# STLINK.net
KiCad netlist of a schematic drawn in Altium Designer
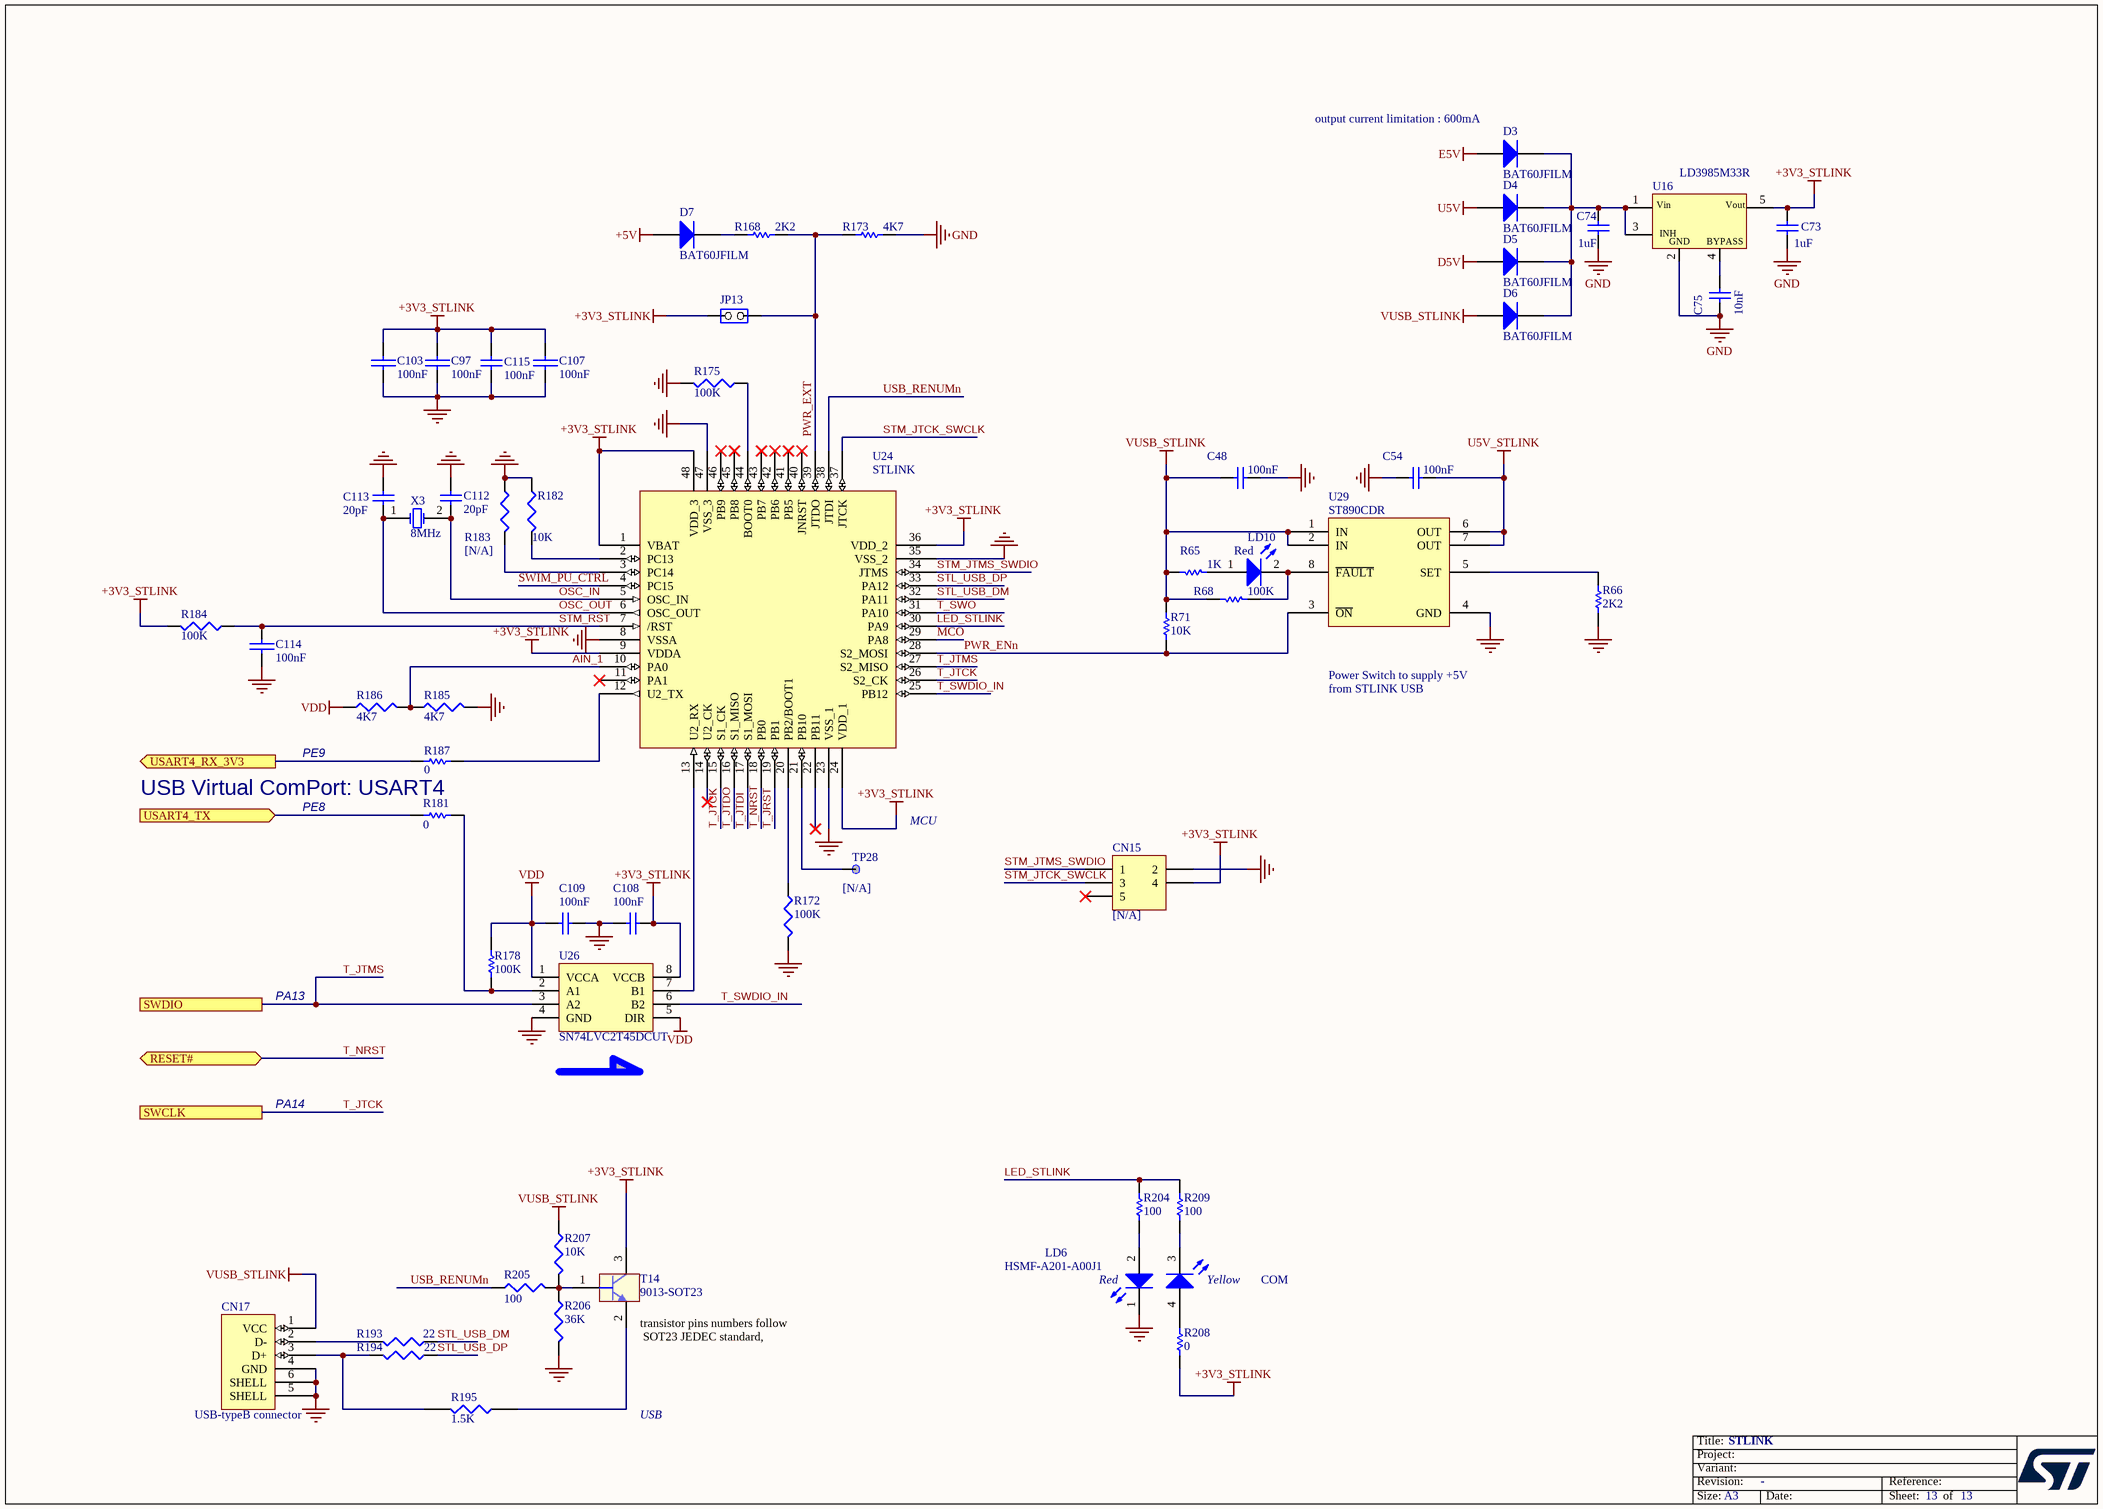
[diagram p0: STLINK.SchDoc]

(export (version "E")
  (design (tool "Eeschema 10.0.6"))
  (components
    (comp (ref "C48")
      (value "100nF")
      (footprint "0402C")
      (description "Capacitor 0402 / 0603 / 0805")
      (libsource (lib "MCD_TOOLS") (part "Capacitor_ST"))
    )
    (comp (ref "C54")
      (value "100nF")
      (footprint "0402C")
      (description "Capacitor 0402 / 0603 / 0805")
      (libsource (lib "MCD_TOOLS") (part "Capacitor_ST"))
    )
    (comp (ref "C73")
      (value "1uF")
      (footprint "0603C")
      (description "Capacitor")
      (fields (field (name "PUBLISHER") "Altium Limited"))
      (libsource (lib "Miscellaneous Devices") (part "CAP"))
    )
    (comp (ref "C74")
      (value "1uF")
      (footprint "0603C")
      (description "Capacitor")
      (fields (field (name "PUBLISHER") "Altium Limited"))
      (libsource (lib "Miscellaneous Devices") (part "CAP"))
    )
    (comp (ref "C75")
      (value "10nF")
      (footprint "0402C")
      (description "Capacitor")
      (fields (field (name "PUBLISHER") "Altium Limited"))
      (libsource (lib "Miscellaneous Devices") (part "Cap"))
    )
    (comp (ref "C97") (value "100nF") (footprint "0402C") (libsource (lib "*") (part "CAP")))
    (comp (ref "C103") (value "100nF") (footprint "0402C") (libsource (lib "*") (part "CAP")))
    (comp (ref "C107") (value "100nF") (footprint "0402C") (libsource (lib "*") (part "CAP")))
    (comp (ref "C108")
      (value "100nF")
      (footprint "0402C")
      (description "Capacitor")
      (fields (field (name "PUBLISHER") "Altium Limited"))
      (libsource (lib "Miscellaneous Devices") (part "CAP"))
    )
    (comp (ref "C109")
      (value "100nF")
      (footprint "0402C")
      (description "Capacitor")
      (fields (field (name "PUBLISHER") "Altium Limited"))
      (libsource (lib "Miscellaneous Devices") (part "CAP"))
    )
    (comp (ref "C112")
      (value "20pF")
      (footprint "0402C")
      (description "Capacitor")
      (fields (field (name "PUBLISHER") "Altium Limited"))
      (libsource (lib "Miscellaneous Devices") (part "CAP"))
    )
    (comp (ref "C113")
      (value "20pF")
      (footprint "0402C")
      (description "Capacitor")
      (fields (field (name "PUBLISHER") "Altium Limited"))
      (libsource (lib "Miscellaneous Devices") (part "CAP"))
    )
    (comp (ref "C114") (value "100nF") (footprint "0402C") (libsource (lib "*") (part "CAP")))
    (comp (ref "C115")
      (value "100nF")
      (footprint "0402C")
      (description "Capacitor")
      (fields (field (name "PUBLISHER") "Altium Limited"))
      (libsource (lib "*") (part "Cap"))
    )
    (comp (ref "CN15")
      (value "[N/A]")
      (footprint "HDR_2X3-1_2R54-6")
      (description "Header, 3-Pin, Dual row")
      (fields (field (name "PUBLISHER") "Altium Limited"))
      (libsource (lib "Miscellaneous Connectors") (part "Header 3X2"))
    )
    (comp (ref "CN17")
      (value "USB-typeB connector")
      (footprint "USB-B")
      (libsource (lib "MB1070") (part "USB-typeB connector"))
    )
    (comp (ref "D3")
      (value "BAT60JFILM")
      (footprint "SOD-323")
      (description "Default Diode")
      (fields (field (name "PUBLISHER") "Altium Limited"))
      (libsource (lib "MB1144_1") (part "Diode"))
    )
    (comp (ref "D4")
      (value "BAT60JFILM")
      (footprint "SOD-323")
      (description "Default Diode")
      (fields (field (name "PUBLISHER") "Altium Limited"))
      (libsource (lib "MB1144_1") (part "Diode"))
    )
    (comp (ref "D5")
      (value "BAT60JFILM")
      (footprint "SOD-323")
      (description "Default Diode")
      (fields (field (name "PUBLISHER") "Altium Limited"))
      (libsource (lib "MB1144_1") (part "Diode"))
    )
    (comp (ref "D6")
      (value "BAT60JFILM")
      (footprint "SOD-323")
      (description "Default Diode")
      (fields (field (name "PUBLISHER") "Altium Limited"))
      (libsource (lib "MB1144_1") (part "Diode"))
    )
    (comp (ref "D7")
      (value "BAT60JFILM")
      (footprint "SOD-323")
      (description "Default Diode")
      (fields (field (name "PUBLISHER") "Altium Limited"))
      (libsource (lib "MB1144_1") (part "Diode"))
    )
    (comp (ref "JP13") (value "~") (footprint "SIP2") (libsource (lib "*") (part "JP2")))
    (comp (ref "LD6")
      (value "HSMF-A201-A00J1")
      (footprint "LED2_3528")
      (fields (field (name "SILKSCREEN") "COM"))
      (libsource (lib "MB819") (part "HSMF-A201-A00J1"))
    )
    (comp (ref "LD10")
      (value "Red")
      (footprint "0603D")
      (description "Typical RED, GREEN, YELLOW, AMBER GaAs LED")
      (fields (field (name "PUBLISHER") "Altium Limited"))
      (libsource (lib "Miscellaneous Devices") (part "LED2"))
    )
    (comp (ref "R65")
      (value "1K")
      (footprint "0402R")
      (description "Resistor")
      (fields (field (name "PUBLISHER") "Altium Limited"))
      (libsource (lib "*") (part "Res1"))
    )
    (comp (ref "R66")
      (value "2K2")
      (footprint "0402R")
      (description "Resistor")
      (fields (field (name "PUBLISHER") "Altium Limited"))
      (libsource (lib "Miscellaneous Devices") (part "res1"))
    )
    (comp (ref "R68")
      (value "100K")
      (footprint "0402R")
      (description "Resistor")
      (fields (field (name "PUBLISHER") "Altium Limited"))
      (libsource (lib "*") (part "Res1"))
    )
    (comp (ref "R71")
      (value "10K")
      (footprint "0402R")
      (description "Resistor")
      (libsource (lib "MCD_TOOLS") (part "Resistor_ST"))
    )
    (comp (ref "R168")
      (value "2K2")
      (footprint "0402R")
      (description "Resistor")
      (fields (field (name "PUBLISHER") "Altium Limited"))
      (libsource (lib "Miscellaneous Devices") (part "res1"))
    )
    (comp (ref "R172")
      (value "100K")
      (footprint "0402R")
      (description "Resistor")
      (libsource (lib "*") (part "RES1"))
    )
    (comp (ref "R173")
      (value "4K7")
      (footprint "0402R")
      (description "Resistor")
      (fields (field (name "PUBLISHER") "Altium Limited"))
      (libsource (lib "Miscellaneous Devices") (part "res1"))
    )
    (comp (ref "R175")
      (value "100K")
      (footprint "0402R")
      (description "Resistor")
      (libsource (lib "*") (part "RES1"))
    )
    (comp (ref "R178")
      (value "100K")
      (footprint "0402R")
      (description "Resistor")
      (fields (field (name "PUBLISHER") "Altium Limited"))
      (libsource (lib "Miscellaneous Devices") (part "Res1"))
    )
    (comp (ref "R181")
      (value "0")
      (footprint "0603R")
      (description "Resistor")
      (fields (field (name "PUBLISHER") "Altium Limited"))
      (libsource (lib "Miscellaneous Devices") (part "Res1"))
    )
    (comp (ref "R182")
      (value "10K")
      (footprint "0402R")
      (description "Resistor")
      (libsource (lib "*") (part "R"))
    )
    (comp (ref "R183") (value "[N/A]") (footprint "0603R") (libsource (lib "*") (part "R")))
    (comp (ref "R184")
      (value "100K")
      (footprint "0402R")
      (description "Resistor")
      (libsource (lib "*") (part "RES1"))
    )
    (comp (ref "R185") (value "4K7") (footprint "0402R") (libsource (lib "*") (part "RES1")))
    (comp (ref "R186") (value "4K7") (footprint "0402R") (libsource (lib "*") (part "RES1")))
    (comp (ref "R187")
      (value "0")
      (footprint "0603R")
      (description "Resistor")
      (fields (field (name "PUBLISHER") "Altium Limited"))
      (libsource (lib "Miscellaneous Devices") (part "Res1"))
    )
    (comp (ref "R193")
      (value "22")
      (footprint "0402R")
      (description "Resistor")
      (libsource (lib "*") (part "RES1"))
    )
    (comp (ref "R194")
      (value "22")
      (footprint "0402R")
      (description "Resistor")
      (libsource (lib "*") (part "RES1"))
    )
    (comp (ref "R195") (value "1.5K") (footprint "0402R") (libsource (lib "") (part "RES1_1")))
    (comp (ref "R204")
      (value "100")
      (footprint "0402R")
      (description "Resistor")
      (fields (field (name "PUBLISHER") "Altium Limited"))
      (libsource (lib "Miscellaneous Devices") (part "Res1"))
    )
    (comp (ref "R205")
      (value "100")
      (footprint "0402R")
      (description "Resistor")
      (libsource (lib "*") (part "R"))
    )
    (comp (ref "R206")
      (value "36K")
      (footprint "0402R")
      (description "Resistor")
      (libsource (lib "*") (part "R"))
    )
    (comp (ref "R207")
      (value "10K")
      (footprint "0402R")
      (description "Resistor")
      (libsource (lib "*") (part "R"))
    )
    (comp (ref "R208")
      (value "0")
      (footprint "0603R")
      (description "Resistor")
      (fields (field (name "PUBLISHER") "Altium Limited"))
      (libsource (lib "Miscellaneous Devices") (part "Res1"))
    )
    (comp (ref "R209")
      (value "100")
      (footprint "0402R")
      (description "Resistor")
      (fields (field (name "PUBLISHER") "Altium Limited"))
      (libsource (lib "Miscellaneous Devices") (part "Res1"))
    )
    (comp (ref "T14")
      (value "9013-SOT23")
      (footprint "SOT-23")
      (description "NPN Bipolar Transistor")
      (libsource (lib "MCD_TOOLS") (part "9013-SOT23"))
    )
    (comp (ref "TP28") (value "[N/A]") (footprint "TP") (libsource (lib "*") (part "TP")))
    (comp (ref "U16")
      (value "LD3985M33R")
      (footprint "SOT23-5")
      (description "Ultra low drop-low noise BiCMOS voltage, regulators low ESR capacitors compatible")
      (libsource (lib "MCD_TOOLS") (part "LD3985M33R"))
    )
    (comp (ref "U24")
      (value "STLINK")
      (footprint "LQFP48_0R5_9X9")
      (libsource (lib "*") (part "STM32F10x(48pin)"))
    )
    (comp (ref "U26")
      (value "SN74LVC2T45DCUT")
      (footprint "USOP8_0R5_2X3R1")
      (libsource (lib "MB818") (part "SN74LVC2T45DCUT"))
    )
    (comp (ref "U29")
      (value "ST890CDR")
      (footprint "SOIC8_1R27_4R9X6")
      (libsource (lib "MB1167") (part "ST890CDR"))
    )
    (comp (ref "X3")
      (value "8MHz")
      (footprint "XTAL_2SM_12R7X4R7")
      (description "Crystal Oscillator")
      (fields (field (name "PUBLISHER") "Altium Limited"))
      (libsource (lib "*") (part "XTAL"))
    )
  )
  (nets
    (net (code "1") (name "+3V3_STLINK") (class "Default")
      (node (ref "C103") (pin "2") (pinfunction "2_2") (pintype "passive"))
      (node (ref "C107") (pin "2") (pinfunction "2_2") (pintype "passive"))
      (node (ref "C108") (pin "1") (pinfunction "1_1") (pintype "passive"))
      (node (ref "C115") (pin "1") (pinfunction "1_1") (pintype "passive"))
      (node (ref "C73") (pin "1") (pinfunction "1_1") (pintype "passive"))
      (node (ref "C97") (pin "2") (pinfunction "2_2") (pintype "passive"))
      (node (ref "CN15") (pin "4") (pinfunction "4_4") (pintype "passive"))
      (node (ref "JP13") (pin "1") (pinfunction "COMMON_1") (pintype "passive"))
      (node (ref "R184") (pin "2") (pinfunction "2_2") (pintype "passive"))
      (node (ref "R208") (pin "2") (pinfunction "2_2") (pintype "passive"))
      (node (ref "T14") (pin "3") (pinfunction "C_3") (pintype "passive"))
      (node (ref "U16") (pin "5") (pinfunction "Vout_5") (pintype "passive"))
      (node (ref "U24") (pin "1") (pinfunction "VBAT_1") (pintype "power_in"))
      (node (ref "U24") (pin "24") (pinfunction "VDD_1_24") (pintype "power_in"))
      (node (ref "U24") (pin "36") (pinfunction "VDD_2_36") (pintype "power_in"))
      (node (ref "U24") (pin "48") (pinfunction "VDD_3_48") (pintype "power_in"))
      (node (ref "U24") (pin "9") (pinfunction "VDDA_9") (pintype "power_in"))
      (node (ref "U26") (pin "8") (pinfunction "VCCB_8") (pintype "passive"))
    )
    (net (code "2") (name "+5V") (class "Default")
      (node (ref "D7") (pin "1") (pinfunction "A_1") (pintype "passive"))
    )
    (net (code "3") (name "/AIN_1") (class "Default")
      (node (ref "R185") (pin "1") (pinfunction "1_1") (pintype "passive"))
      (node (ref "R186") (pin "2") (pinfunction "2_2") (pintype "passive"))
      (node (ref "U24") (pin "10") (pinfunction "PA0_10") (pintype "bidirectional"))
    )
    (net (code "4") (name "/LED_STLINK") (class "Default")
      (node (ref "R204") (pin "1") (pinfunction "1_1") (pintype "passive"))
      (node (ref "R209") (pin "1") (pinfunction "1_1") (pintype "passive"))
      (node (ref "U24") (pin "30") (pinfunction "PA9_30") (pintype "bidirectional"))
    )
    (net (code "5") (name "/MCO") (class "Default")
      (node (ref "U24") (pin "29") (pinfunction "PA8_29") (pintype "bidirectional"))
    )
    (net (code "6") (name "/OSC_IN") (class "Default")
      (node (ref "C112") (pin "2") (pinfunction "2_2") (pintype "passive"))
      (node (ref "U24") (pin "5") (pinfunction "OSC_IN_5") (pintype "input"))
      (node (ref "X3") (pin "2") (pinfunction "OSC2_2") (pintype "passive"))
    )
    (net (code "7") (name "/OSC_OUT") (class "Default")
      (node (ref "C113") (pin "2") (pinfunction "2_2") (pintype "passive"))
      (node (ref "U24") (pin "6") (pinfunction "OSC_OUT_6") (pintype "output"))
      (node (ref "X3") (pin "1") (pinfunction "OSC1_1") (pintype "passive"))
    )
    (net (code "8") (name "/PWR_ENn") (class "Default")
      (node (ref "R71") (pin "1") (pinfunction "1_1") (pintype "passive"))
      (node (ref "U24") (pin "28") (pinfunction "S2_MOSI_28") (pintype "bidirectional"))
      (node (ref "U29") (pin "3") (pinfunction "~{ON}_3") (pintype "passive"))
    )
    (net (code "9") (name "/PWR_EXT") (class "Default")
      (node (ref "JP13") (pin "2") (pinfunction "NO_2") (pintype "passive"))
      (node (ref "R168") (pin "1") (pinfunction "1_1") (pintype "passive"))
      (node (ref "R173") (pin "2") (pinfunction "2_2") (pintype "passive"))
      (node (ref "U24") (pin "39") (pinfunction "JTDO_39") (pintype "bidirectional"))
    )
    (net (code "10") (name "/STL_USB_DM") (class "Default")
      (node (ref "R193") (pin "1") (pinfunction "1_1") (pintype "passive"))
      (node (ref "U24") (pin "32") (pinfunction "PA11_32") (pintype "bidirectional"))
    )
    (net (code "11") (name "/STL_USB_DP") (class "Default")
      (node (ref "R194") (pin "1") (pinfunction "1_1") (pintype "passive"))
      (node (ref "U24") (pin "33") (pinfunction "PA12_33") (pintype "bidirectional"))
    )
    (net (code "12") (name "/STM_JTCK_SWCLK") (class "Default")
      (node (ref "CN15") (pin "3") (pinfunction "3_3") (pintype "passive"))
      (node (ref "U24") (pin "37") (pinfunction "JTCK_37") (pintype "bidirectional"))
    )
    (net (code "13") (name "/STM_JTMS_SWDIO") (class "Default")
      (node (ref "CN15") (pin "1") (pinfunction "1_1") (pintype "passive"))
      (node (ref "U24") (pin "34") (pinfunction "JTMS_34") (pintype "bidirectional"))
    )
    (net (code "14") (name "/STM_RST") (class "Default")
      (node (ref "C114") (pin "2") (pinfunction "2_2") (pintype "passive"))
      (node (ref "R184") (pin "1") (pinfunction "1_1") (pintype "passive"))
      (node (ref "U24") (pin "7") (pinfunction "/RST_7") (pintype "input"))
    )
    (net (code "15") (name "/SWIM_PU_CTRL") (class "Default")
      (node (ref "U24") (pin "4") (pinfunction "PC15_4") (pintype "bidirectional"))
    )
    (net (code "16") (name "/T_JRST") (class "Default")
      (node (ref "U24") (pin "19") (pinfunction "PB1_19") (pintype "bidirectional"))
    )
    (net (code "17") (name "/T_JTCK") (class "Default")
      (node (ref "U24") (pin "15") (pinfunction "S1_CK_15") (pintype "bidirectional"))
      (node (ref "U24") (pin "26") (pinfunction "S2_CK_26") (pintype "bidirectional"))
    )
    (net (code "18") (name "/T_JTDI") (class "Default")
      (node (ref "U24") (pin "17") (pinfunction "S1_MOSI_17") (pintype "bidirectional"))
    )
    (net (code "19") (name "/T_JTDO") (class "Default")
      (node (ref "U24") (pin "16") (pinfunction "S1_MISO_16") (pintype "bidirectional"))
    )
    (net (code "20") (name "/T_JTMS") (class "Default")
      (node (ref "U24") (pin "27") (pinfunction "S2_MISO_27") (pintype "bidirectional"))
      (node (ref "U26") (pin "3") (pinfunction "A2_3") (pintype "passive"))
    )
    (net (code "21") (name "/T_NRST") (class "Default")
      (node (ref "U24") (pin "18") (pinfunction "PB0_18") (pintype "bidirectional"))
    )
    (net (code "22") (name "/T_SWDIO_IN") (class "Default")
      (node (ref "U24") (pin "25") (pinfunction "PB12_25") (pintype "bidirectional"))
      (node (ref "U26") (pin "6") (pinfunction "B2_6") (pintype "passive"))
    )
    (net (code "23") (name "/T_SWO") (class "Default")
      (node (ref "U24") (pin "31") (pinfunction "PA10_31") (pintype "bidirectional"))
    )
    (net (code "24") (name "/USART4_RX_3V3") (class "Default")
      (node (ref "R187") (pin "2") (pinfunction "2_2") (pintype "passive"))
    )
    (net (code "25") (name "/USART4_TX") (class "Default")
      (node (ref "R181") (pin "1") (pinfunction "1_1") (pintype "passive"))
    )
    (net (code "26") (name "/USB_RENUMn") (class "Default")
      (node (ref "R205") (pin "1") (pinfunction "1_1") (pintype "passive"))
      (node (ref "U24") (pin "38") (pinfunction "JTDI_38") (pintype "bidirectional"))
    )
    (net (code "27") (name "D5V") (class "Default")
      (node (ref "D5") (pin "1") (pinfunction "A_1") (pintype "passive"))
    )
    (net (code "28") (name "E5V") (class "Default")
      (node (ref "D3") (pin "1") (pinfunction "A_1") (pintype "passive"))
    )
    (net (code "29") (name "GND") (class "Default")
      (node (ref "C103") (pin "1") (pinfunction "1_1") (pintype "passive"))
      (node (ref "C107") (pin "1") (pinfunction "1_1") (pintype "passive"))
      (node (ref "C108") (pin "2") (pinfunction "2_2") (pintype "passive"))
      (node (ref "C109") (pin "2") (pinfunction "2_2") (pintype "passive"))
      (node (ref "C112") (pin "1") (pinfunction "1_1") (pintype "passive"))
      (node (ref "C113") (pin "1") (pinfunction "1_1") (pintype "passive"))
      (node (ref "C114") (pin "1") (pinfunction "1_1") (pintype "passive"))
      (node (ref "C115") (pin "2") (pinfunction "2_2") (pintype "passive"))
      (node (ref "C48") (pin "2") (pinfunction "2_2") (pintype "passive"))
      (node (ref "C54") (pin "1") (pinfunction "1_1") (pintype "passive"))
      (node (ref "C73") (pin "2") (pinfunction "2_2") (pintype "passive"))
      (node (ref "C74") (pin "2") (pinfunction "2_2") (pintype "passive"))
      (node (ref "C75") (pin "2") (pinfunction "2_2") (pintype "passive"))
      (node (ref "C97") (pin "1") (pinfunction "1_1") (pintype "passive"))
      (node (ref "CN15") (pin "2") (pinfunction "2_2") (pintype "passive"))
      (node (ref "CN17") (pin "4") (pinfunction "GND_4") (pintype "passive"))
      (node (ref "CN17") (pin "5") (pinfunction "SHELL_5") (pintype "power_in"))
      (node (ref "CN17") (pin "6") (pinfunction "SHELL_6") (pintype "power_in"))
      (node (ref "LD6") (pin "1") (pinfunction "RED_cathode_1") (pintype "passive"))
      (node (ref "R172") (pin "2") (pinfunction "2_2") (pintype "passive"))
      (node (ref "R173") (pin "1") (pinfunction "1_1") (pintype "passive"))
      (node (ref "R175") (pin "2") (pinfunction "2_2") (pintype "passive"))
      (node (ref "R182") (pin "1") (pinfunction "1_1") (pintype "passive"))
      (node (ref "R183") (pin "1") (pinfunction "1_1") (pintype "passive"))
      (node (ref "R185") (pin "2") (pinfunction "2_2") (pintype "passive"))
      (node (ref "R206") (pin "2") (pinfunction "2_2") (pintype "passive"))
      (node (ref "R66") (pin "2") (pinfunction "2_2") (pintype "passive"))
      (node (ref "U16") (pin "2") (pinfunction "GND_2") (pintype "passive"))
      (node (ref "U24") (pin "23") (pinfunction "VSS_1_23") (pintype "passive"))
      (node (ref "U24") (pin "35") (pinfunction "VSS_2_35") (pintype "passive"))
      (node (ref "U24") (pin "47") (pinfunction "VSS_3_47") (pintype "passive"))
      (node (ref "U24") (pin "8") (pinfunction "VSSA_8") (pintype "passive"))
      (node (ref "U26") (pin "4") (pinfunction "GND_4") (pintype "passive"))
      (node (ref "U29") (pin "4") (pinfunction "GND_4") (pintype "passive"))
    )
    (net (code "30") (name "Net-(CN17-D+)") (class "Default")
      (node (ref "CN17") (pin "3") (pinfunction "D+_3") (pintype "bidirectional"))
      (node (ref "R194") (pin "2") (pinfunction "2_2") (pintype "passive"))
      (node (ref "R195") (pin "2") (pinfunction "2_2") (pintype "passive"))
    )
    (net (code "31") (name "Net-(CN17-D-)") (class "Default")
      (node (ref "CN17") (pin "2") (pinfunction "D-_2") (pintype "bidirectional"))
      (node (ref "R193") (pin "2") (pinfunction "2_2") (pintype "passive"))
    )
    (net (code "32") (name "Net-(D3-K)") (class "Default")
      (node (ref "C74") (pin "1") (pinfunction "1_1") (pintype "passive"))
      (node (ref "D3") (pin "2") (pinfunction "K_2") (pintype "passive"))
      (node (ref "D4") (pin "2") (pinfunction "K_2") (pintype "passive"))
      (node (ref "D5") (pin "2") (pinfunction "K_2") (pintype "passive"))
      (node (ref "D6") (pin "2") (pinfunction "K_2") (pintype "passive"))
      (node (ref "U16") (pin "1") (pinfunction "Vin_1") (pintype "passive"))
      (node (ref "U16") (pin "3") (pinfunction "CE_3") (pintype "passive"))
    )
    (net (code "33") (name "Net-(D7-K)") (class "Default")
      (node (ref "D7") (pin "2") (pinfunction "K_2") (pintype "passive"))
      (node (ref "R168") (pin "2") (pinfunction "2_2") (pintype "passive"))
    )
    (net (code "34") (name "Net-(LD6-Red_anode)") (class "Default")
      (node (ref "LD6") (pin "2") (pinfunction "Red_anode_2") (pintype "passive"))
      (node (ref "R204") (pin "2") (pinfunction "2_2") (pintype "passive"))
    )
    (net (code "35") (name "Net-(LD6-YellowGreen_anode)") (class "Default")
      (node (ref "LD6") (pin "4") (pinfunction "YellowGreen_anode_4") (pintype "passive"))
      (node (ref "R208") (pin "1") (pinfunction "1_1") (pintype "passive"))
    )
    (net (code "36") (name "Net-(LD6-YellowGreen_cathode)") (class "Default")
      (node (ref "LD6") (pin "3") (pinfunction "YellowGreen_cathode_3") (pintype "passive"))
      (node (ref "R209") (pin "2") (pinfunction "2_2") (pintype "passive"))
    )
    (net (code "37") (name "Net-(LD10-A)") (class "Default")
      (node (ref "LD10") (pin "1") (pinfunction "A_1") (pintype "passive"))
      (node (ref "R65") (pin "2") (pinfunction "2_2") (pintype "passive"))
    )
    (net (code "38") (name "Net-(LD10-K)") (class "Default")
      (node (ref "LD10") (pin "2") (pinfunction "K_2") (pintype "passive"))
      (node (ref "R68") (pin "2") (pinfunction "2_2") (pintype "passive"))
      (node (ref "U29") (pin "8") (pinfunction "~{FAULT}_8") (pintype "passive"))
    )
    (net (code "39") (name "Net-(T14-B)") (class "Default")
      (node (ref "R205") (pin "2") (pinfunction "2_2") (pintype "passive"))
      (node (ref "R206") (pin "1") (pinfunction "1_1") (pintype "passive"))
      (node (ref "R207") (pin "2") (pinfunction "2_2") (pintype "passive"))
      (node (ref "T14") (pin "1") (pinfunction "B_1") (pintype "passive"))
    )
    (net (code "40") (name "Net-(T14-E)") (class "Default")
      (node (ref "R195") (pin "1") (pinfunction "1_1") (pintype "passive"))
      (node (ref "T14") (pin "2") (pinfunction "E_2") (pintype "passive"))
    )
    (net (code "41") (name "Net-(U16-BYPASS)") (class "Default")
      (node (ref "C75") (pin "1") (pinfunction "1_1") (pintype "passive"))
      (node (ref "U16") (pin "4") (pinfunction "BYPASS_4") (pintype "passive"))
    )
    (net (code "42") (name "Net-(U24-BOOT0)") (class "Default")
      (node (ref "R175") (pin "1") (pinfunction "1_1") (pintype "passive"))
      (node (ref "U24") (pin "44") (pinfunction "BOOT0_44") (pintype "bidirectional"))
    )
    (net (code "43") (name "Net-(U24-PB2{slash}BOOT1)") (class "Default")
      (node (ref "R172") (pin "1") (pinfunction "1_1") (pintype "passive"))
      (node (ref "U24") (pin "20") (pinfunction "PB2/BOOT1_20") (pintype "passive"))
    )
    (net (code "44") (name "Net-(U24-PB10)") (class "Default")
      (node (ref "TP28") (pin "1") (pinfunction "1_1") (pintype "passive"))
      (node (ref "U24") (pin "21") (pinfunction "PB10_21") (pintype "bidirectional"))
    )
    (net (code "45") (name "Net-(U24-PC13)") (class "Default")
      (node (ref "R182") (pin "2") (pinfunction "2_2") (pintype "passive"))
      (node (ref "U24") (pin "2") (pinfunction "PC13_2") (pintype "bidirectional"))
    )
    (net (code "46") (name "Net-(U24-PC14)") (class "Default")
      (node (ref "R183") (pin "2") (pinfunction "2_2") (pintype "passive"))
      (node (ref "U24") (pin "3") (pinfunction "PC14_3") (pintype "bidirectional"))
    )
    (net (code "47") (name "Net-(U24-U2_RX)") (class "Default")
      (node (ref "U24") (pin "13") (pinfunction "U2_RX_13") (pintype "input"))
      (node (ref "U26") (pin "7") (pinfunction "B1_7") (pintype "passive"))
    )
    (net (code "48") (name "Net-(U24-U2_TX)") (class "Default")
      (node (ref "R187") (pin "1") (pinfunction "1_1") (pintype "passive"))
      (node (ref "U24") (pin "12") (pinfunction "U2_TX_12") (pintype "output"))
    )
    (net (code "49") (name "Net-(U26-A1)") (class "Default")
      (node (ref "R178") (pin "2") (pinfunction "2_2") (pintype "passive"))
      (node (ref "R181") (pin "2") (pinfunction "2_2") (pintype "passive"))
      (node (ref "U26") (pin "2") (pinfunction "A1_2") (pintype "passive"))
    )
    (net (code "50") (name "Net-(U29-SET)") (class "Default")
      (node (ref "R66") (pin "1") (pinfunction "1_1") (pintype "passive"))
      (node (ref "U29") (pin "5") (pinfunction "SET_5") (pintype "passive"))
    )
    (net (code "51") (name "U5V") (class "Default")
      (node (ref "D4") (pin "1") (pinfunction "A_1") (pintype "passive"))
    )
    (net (code "52") (name "U5V_STLINK") (class "Default")
      (node (ref "C54") (pin "2") (pinfunction "2_2") (pintype "passive"))
      (node (ref "U29") (pin "6") (pinfunction "OUT_6") (pintype "passive"))
      (node (ref "U29") (pin "7") (pinfunction "OUT_7") (pintype "passive"))
    )
    (net (code "53") (name "VDD") (class "Default")
      (node (ref "C109") (pin "1") (pinfunction "1_1") (pintype "passive"))
      (node (ref "R178") (pin "1") (pinfunction "1_1") (pintype "passive"))
      (node (ref "R186") (pin "1") (pinfunction "1_1") (pintype "passive"))
      (node (ref "U26") (pin "1") (pinfunction "VCCA_1") (pintype "passive"))
      (node (ref "U26") (pin "5") (pinfunction "DIR_5") (pintype "passive"))
    )
    (net (code "54") (name "VUSB_STLINK") (class "Default")
      (node (ref "C48") (pin "1") (pinfunction "1_1") (pintype "passive"))
      (node (ref "CN17") (pin "1") (pinfunction "VCC_1") (pintype "bidirectional"))
      (node (ref "D6") (pin "1") (pinfunction "A_1") (pintype "passive"))
      (node (ref "R207") (pin "1") (pinfunction "1_1") (pintype "passive"))
      (node (ref "R65") (pin "1") (pinfunction "1_1") (pintype "passive"))
      (node (ref "R68") (pin "1") (pinfunction "1_1") (pintype "passive"))
      (node (ref "R71") (pin "2") (pinfunction "2_2") (pintype "passive"))
      (node (ref "U29") (pin "1") (pinfunction "IN_1") (pintype "passive"))
      (node (ref "U29") (pin "2") (pinfunction "IN_2") (pintype "passive"))
    )
    (net (code "55") (name "unconnected-(CN15-Pad5)") (class "Default")
      (node (ref "CN15") (pin "5") (pinfunction "5_5") (pintype "passive+no_connect"))
    )
    (net (code "56") (name "unconnected-(U24-JNRST-Pad40)") (class "Default")
      (node (ref "U24") (pin "40") (pinfunction "JNRST_40") (pintype "bidirectional+no_connect"))
    )
    (net (code "57") (name "unconnected-(U24-PA1-Pad11)") (class "Default")
      (node (ref "U24") (pin "11") (pinfunction "PA1_11") (pintype "bidirectional+no_connect"))
    )
    (net (code "58") (name "unconnected-(U24-PB5-Pad41)") (class "Default")
      (node (ref "U24") (pin "41") (pinfunction "PB5_41") (pintype "bidirectional+no_connect"))
    )
    (net (code "59") (name "unconnected-(U24-PB6-Pad42)") (class "Default")
      (node (ref "U24") (pin "42") (pinfunction "PB6_42") (pintype "bidirectional+no_connect"))
    )
    (net (code "60") (name "unconnected-(U24-PB7-Pad43)") (class "Default")
      (node (ref "U24") (pin "43") (pinfunction "PB7_43") (pintype "bidirectional+no_connect"))
    )
    (net (code "61") (name "unconnected-(U24-PB8-Pad45)") (class "Default")
      (node (ref "U24") (pin "45") (pinfunction "PB8_45") (pintype "bidirectional+no_connect"))
    )
    (net (code "62") (name "unconnected-(U24-PB9-Pad46)") (class "Default")
      (node (ref "U24") (pin "46") (pinfunction "PB9_46") (pintype "bidirectional+no_connect"))
    )
    (net (code "63") (name "unconnected-(U24-PB11-Pad22)") (class "Default")
      (node (ref "U24") (pin "22") (pinfunction "PB11_22") (pintype "passive+no_connect"))
    )
    (net (code "64") (name "unconnected-(U24-U2_CK-Pad14)") (class "Default")
      (node (ref "U24") (pin "14") (pinfunction "U2_CK_14") (pintype "bidirectional+no_connect"))
    )
  )
)
